# Spannungsversorgung.net
KiCad netlist of a schematic drawn in EAGLE
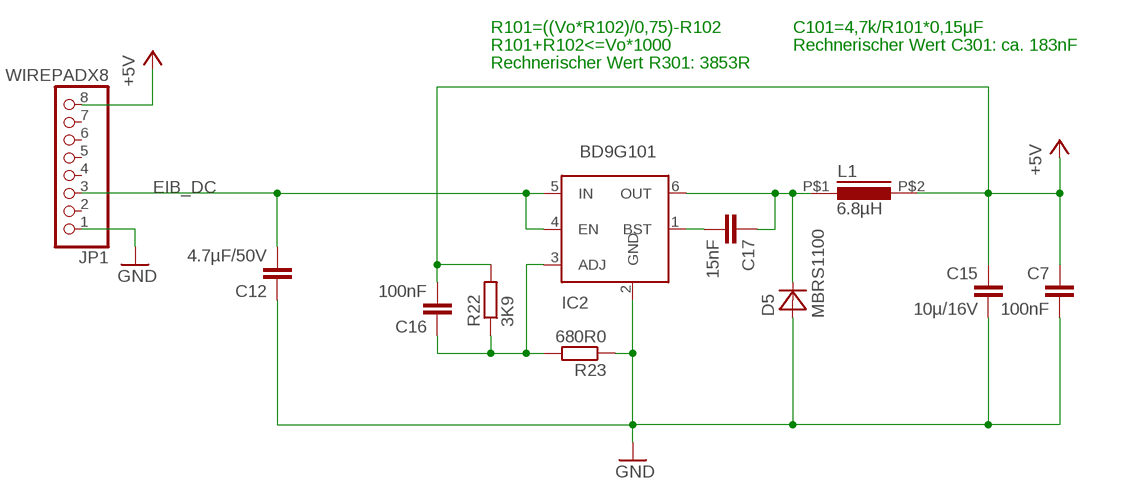
[diagram p0: schematic, sheet 1]

(export (version "E")
  (design (tool "Eeschema 10.0.6"))
  (components
    (comp (ref "C7")
      (value "100nF")
      (footprint "eagle-import:C1206")
      (libsource (lib "eagle-import") (part "C-EUC1206"))
    )
    (comp (ref "C12")
      (value "4.7µF/50V")
      (footprint "eagle-import:C1206")
      (libsource (lib "eagle-import") (part "C-EUC1206"))
    )
    (comp (ref "C15")
      (value "10µ/16V")
      (footprint "eagle-import:C1206")
      (libsource (lib "eagle-import") (part "C-EUC1206"))
    )
    (comp (ref "C16")
      (value "100nF")
      (footprint "eagle-import:C1206")
      (libsource (lib "eagle-import") (part "C-EUC1206"))
    )
    (comp (ref "C17")
      (value "15nF")
      (footprint "eagle-import:C1206")
      (libsource (lib "eagle-import") (part "C-EUC1206"))
    )
    (comp (ref "D5")
      (value "MBRS1100")
      (footprint "eagle-import:SMA")
      (libsource (lib "eagle-import") (part "MBRA340T3"))
    )
    (comp (ref "IC2")
      (value "BD9G101")
      (footprint "eagle-import:SOT23-6")
      (libsource (lib "eagle-import") (part "BD9G101GBD9G101G-SOT23-6"))
    )
    (comp (ref "JP1")
      (value "WIREPADX8")
      (footprint "eagle-import:SMD1,27X2,54X8")
      (libsource (lib "eagle-import") (part "WIREPADX8"))
    )
    (comp (ref "L1")
      (value "6.8µH")
      (footprint "eagle-import:PIS2812")
      (libsource (lib "eagle-import") (part "IND_FASTRON_1616FPS"))
    )
    (comp (ref "R22")
      (value "3K9")
      (footprint "eagle-import:R1206")
      (libsource (lib "eagle-import") (part "R-EU_R1206"))
    )
    (comp (ref "R23")
      (value "680R0")
      (footprint "eagle-import:R1206")
      (libsource (lib "eagle-import") (part "R-EU_R1206"))
    )
  )
  (nets
    (net (code "1") (name "+5V") (class "Default")
      (node (ref "C15") (pin "1") (pinfunction "1_1") (pintype "passive"))
      (node (ref "C16") (pin "2") (pinfunction "2_2") (pintype "passive"))
      (node (ref "C7") (pin "1") (pinfunction "1_1") (pintype "passive"))
      (node (ref "JP1") (pin "8") (pinfunction "8_8") (pintype "passive"))
      (node (ref "L1") (pin "P$2") (pinfunction "2_P$2") (pintype "passive"))
      (node (ref "R22") (pin "2") (pinfunction "2_2") (pintype "passive"))
    )
    (net (code "2") (name "/EIB_DC") (class "Default")
      (node (ref "C12") (pin "2") (pinfunction "2_2") (pintype "passive"))
      (node (ref "IC2") (pin "4") (pinfunction "EN_4") (pintype "input"))
      (node (ref "IC2") (pin "5") (pinfunction "IN_5") (pintype "input"))
      (node (ref "JP1") (pin "3") (pinfunction "3_3") (pintype "passive"))
    )
    (net (code "3") (name "GND") (class "Default")
      (node (ref "C12") (pin "1") (pinfunction "1_1") (pintype "passive"))
      (node (ref "C15") (pin "2") (pinfunction "2_2") (pintype "passive"))
      (node (ref "C7") (pin "2") (pinfunction "2_2") (pintype "passive"))
      (node (ref "D5") (pin "A") (pinfunction "A_A") (pintype "passive"))
      (node (ref "IC2") (pin "2") (pinfunction "GND_2") (pintype "power_in"))
      (node (ref "JP1") (pin "1") (pinfunction "1_1") (pintype "passive"))
      (node (ref "R23") (pin "1") (pinfunction "1_1") (pintype "passive"))
    )
    (net (code "4") (name "Net-(IC2-ADJ)") (class "Default")
      (node (ref "C16") (pin "1") (pinfunction "1_1") (pintype "passive"))
      (node (ref "IC2") (pin "3") (pinfunction "ADJ_3") (pintype "passive"))
      (node (ref "R22") (pin "1") (pinfunction "1_1") (pintype "passive"))
      (node (ref "R23") (pin "2") (pinfunction "2_2") (pintype "passive"))
    )
    (net (code "5") (name "Net-(IC2-BST)") (class "Default")
      (node (ref "C17") (pin "2") (pinfunction "2_2") (pintype "passive"))
      (node (ref "IC2") (pin "1") (pinfunction "BST_1") (pintype "output"))
    )
    (net (code "6") (name "Net-(IC2-OUT)") (class "Default")
      (node (ref "C17") (pin "1") (pinfunction "1_1") (pintype "passive"))
      (node (ref "D5") (pin "C") (pinfunction "C_C") (pintype "passive"))
      (node (ref "IC2") (pin "6") (pinfunction "OUT_6") (pintype "output"))
      (node (ref "L1") (pin "P$1") (pinfunction "1_P$1") (pintype "passive"))
    )
    (net (code "7") (name "unconnected-(JP1-Pad2)") (class "Default")
      (node (ref "JP1") (pin "2") (pinfunction "2_2") (pintype "passive"))
    )
    (net (code "8") (name "unconnected-(JP1-Pad4)") (class "Default")
      (node (ref "JP1") (pin "4") (pinfunction "4_4") (pintype "passive"))
    )
    (net (code "9") (name "unconnected-(JP1-Pad5)") (class "Default")
      (node (ref "JP1") (pin "5") (pinfunction "5_5") (pintype "passive"))
    )
    (net (code "10") (name "unconnected-(JP1-Pad6)") (class "Default")
      (node (ref "JP1") (pin "6") (pinfunction "6_6") (pintype "passive"))
    )
    (net (code "11") (name "unconnected-(JP1-Pad7)") (class "Default")
      (node (ref "JP1") (pin "7") (pinfunction "7_7") (pintype "passive"))
    )
  )
)
